# ESP32.net
KiCad netlist of a schematic drawn in Altium Designer
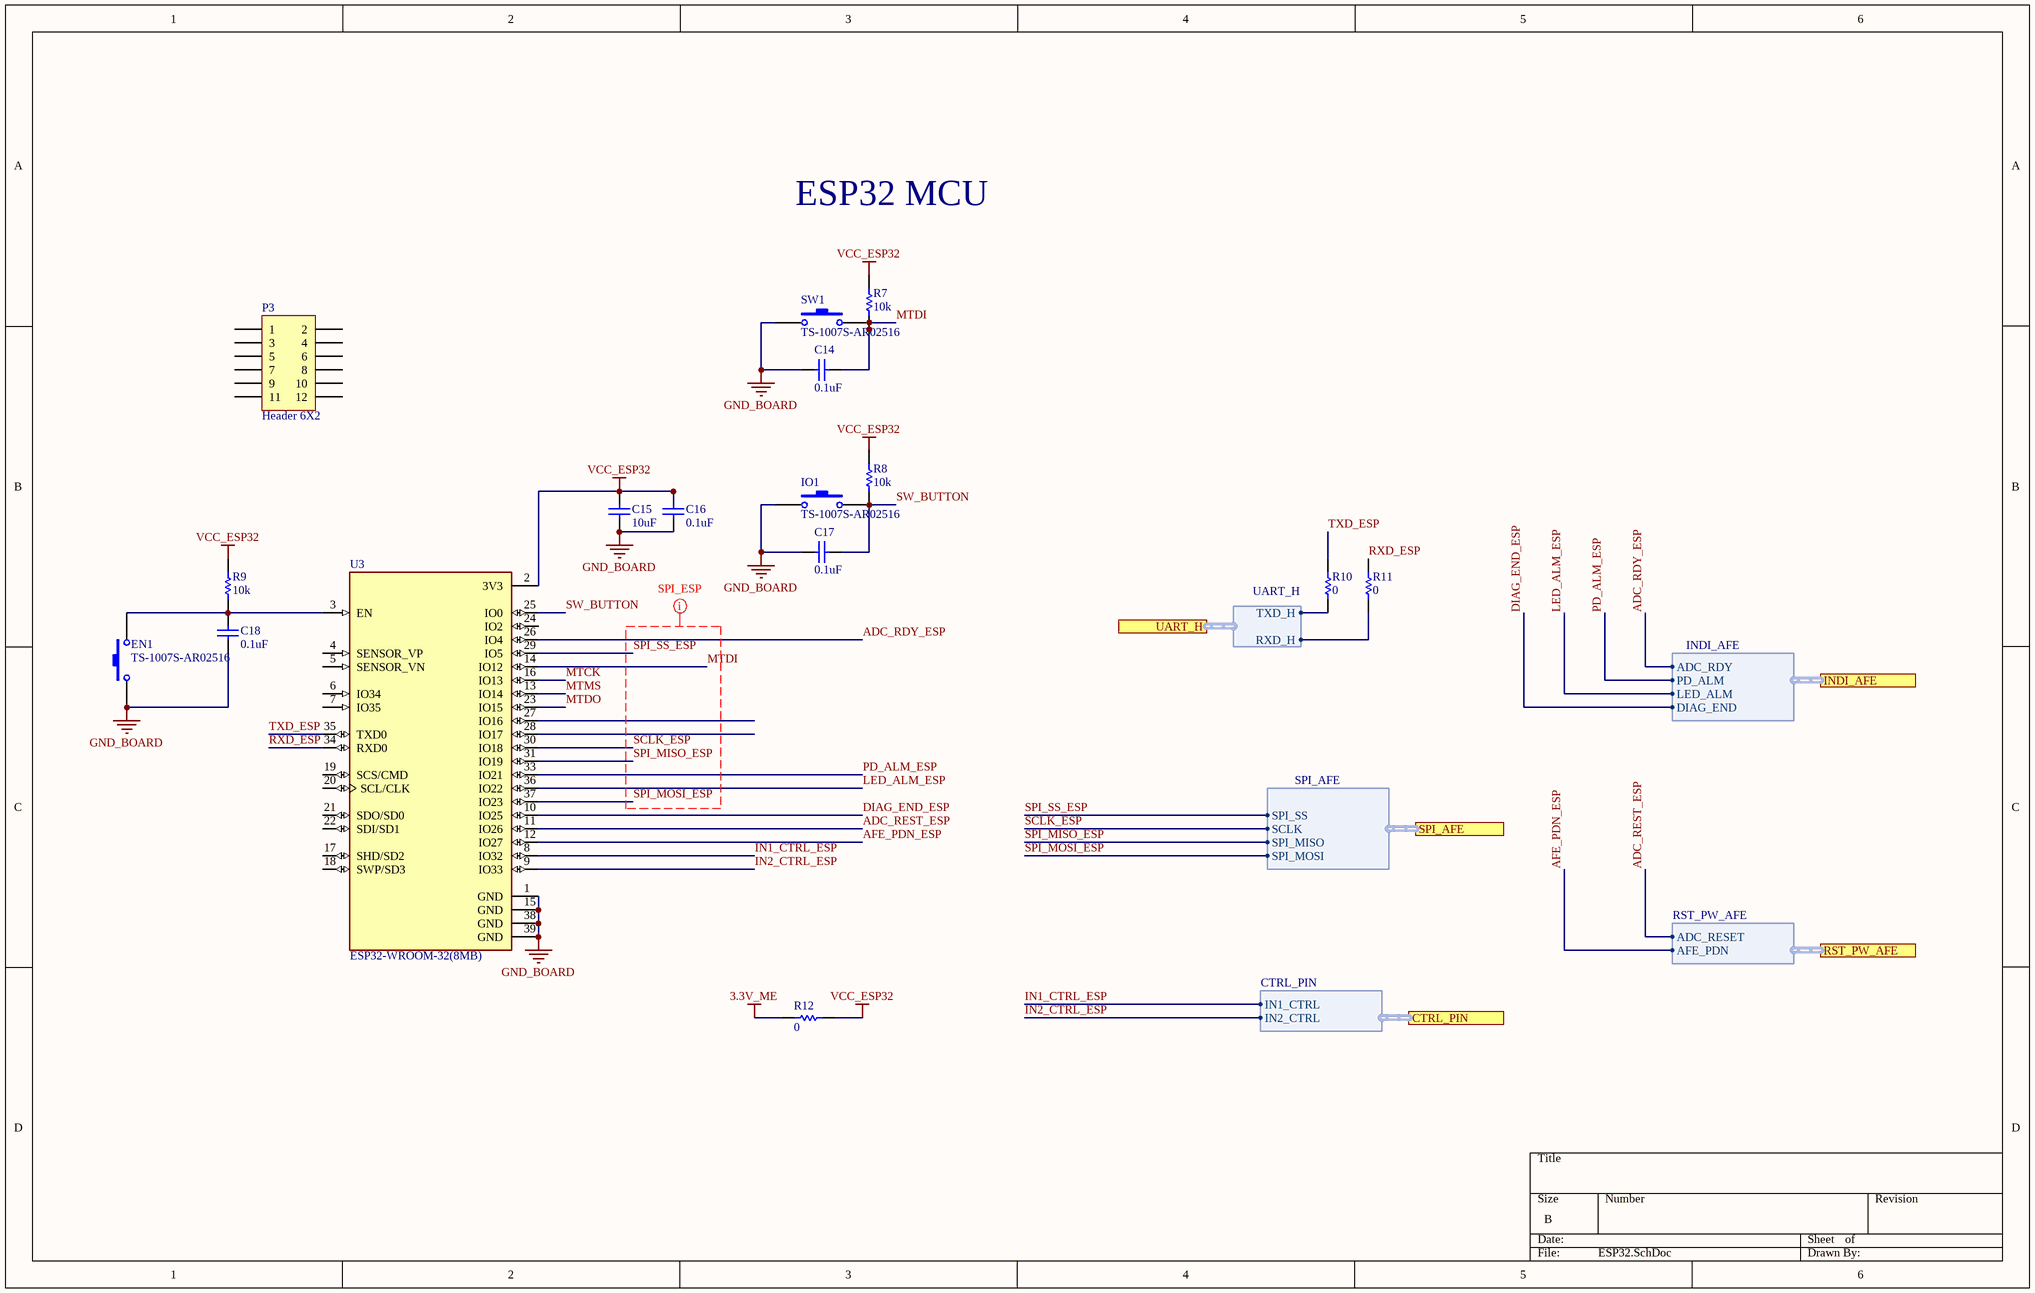
[diagram p0: ESP32.SchDoc]

(export (version "E")
  (design (tool "Eeschema 10.0.6"))
  (components
    (comp (ref "C14")
      (value "0.1uF")
      (footprint "RES-SMD-0603")
      (description "Capacitor")
      (fields (field (name "Comment") "Cap") (field (name "PUBLISHER") "Altium Limited"))
      (libsource (lib "Miscellaneous Devices") (part "Cap"))
    )
    (comp (ref "C15")
      (value "10uF")
      (footprint "RES-SMD-0603")
      (description "Capacitor")
      (fields (field (name "Comment") "Cap") (field (name "PUBLISHER") "Altium Limited"))
      (libsource (lib "Miscellaneous Devices") (part "Cap"))
    )
    (comp (ref "C16")
      (value "0.1uF")
      (footprint "RES-SMD-0603")
      (description "Capacitor")
      (fields (field (name "Comment") "Cap") (field (name "PUBLISHER") "Altium Limited"))
      (libsource (lib "Miscellaneous Devices") (part "Cap"))
    )
    (comp (ref "C17")
      (value "0.1uF")
      (footprint "RES-SMD-0603")
      (description "Capacitor")
      (fields (field (name "Comment") "Cap") (field (name "PUBLISHER") "Altium Limited"))
      (libsource (lib "Miscellaneous Devices") (part "Cap"))
    )
    (comp (ref "C18")
      (value "0.1uF")
      (footprint "RES-SMD-0603")
      (description "Capacitor")
      (fields (field (name "Comment") "Cap") (field (name "PUBLISHER") "Altium Limited"))
      (libsource (lib "Miscellaneous Devices") (part "Cap"))
    )
    (comp (ref "EN1")
      (value "TS-1007S-AR02516")
      (footprint "SW1_SMD")
      (description "Switch")
      (fields (field (name "PUBLISHER") "Altium Limited"))
      (libsource (lib "Miscellaneous Devices") (part "SW-PB"))
    )
    (comp (ref "IO1")
      (value "TS-1007S-AR02516")
      (footprint "SW1_SMD")
      (description "Switch")
      (fields (field (name "PUBLISHER") "Altium Limited"))
      (libsource (lib "Miscellaneous Devices") (part "SW-PB"))
    )
    (comp (ref "P3")
      (value "Header 6X2")
      (footprint "HDR2X6")
      (description "Header, 6-Pin, Dual row")
      (fields (field (name "PUBLISHER") "Altium Limited"))
      (libsource (lib "Miscellaneous Connectors") (part "Header 6X2"))
    )
    (comp (ref "R7")
      (value "10k")
      (footprint "RES-SMD-0603")
      (description "Resistor")
      (fields (field (name "Comment") "Res1") (field (name "PUBLISHER") "Altium Limited"))
      (libsource (lib "Miscellaneous Devices") (part "Res1"))
    )
    (comp (ref "R8")
      (value "10k")
      (footprint "RES-SMD-0603")
      (description "Resistor")
      (fields (field (name "Comment") "Res1") (field (name "PUBLISHER") "Altium Limited"))
      (libsource (lib "Miscellaneous Devices") (part "Res1"))
    )
    (comp (ref "R9")
      (value "10k")
      (footprint "RES-SMD-0603")
      (description "Resistor")
      (fields (field (name "Comment") "Res1") (field (name "PUBLISHER") "Altium Limited"))
      (libsource (lib "Miscellaneous Devices") (part "Res1"))
    )
    (comp (ref "R10")
      (value "0")
      (footprint "RES-SMD-0603")
      (description "Resistor")
      (fields (field (name "Comment") "Res1") (field (name "PUBLISHER") "Altium Limited"))
      (libsource (lib "Miscellaneous Devices") (part "Res1"))
    )
    (comp (ref "R11")
      (value "0")
      (footprint "RES-SMD-0603")
      (description "Resistor")
      (fields (field (name "Comment") "Res1") (field (name "PUBLISHER") "Altium Limited"))
      (libsource (lib "Miscellaneous Devices") (part "Res1"))
    )
    (comp (ref "R12")
      (value "0")
      (footprint "RES-SMD-0603")
      (description "Resistor")
      (fields (field (name "Comment") "Res1") (field (name "PUBLISHER") "Altium Limited"))
      (libsource (lib "Miscellaneous Devices") (part "Res1"))
    )
    (comp (ref "SW1")
      (value "TS-1007S-AR02516")
      (footprint "SW1_SMD")
      (description "Switch")
      (fields (field (name "PUBLISHER") "Altium Limited"))
      (libsource (lib "Miscellaneous Devices") (part "SW-PB"))
    )
    (comp (ref "U3")
      (value "ESP32-WROOM-32(8MB)")
      (footprint "MODULE_ESP32-WROOM-32(8MB)")
      (fields (field (name "MF") "Espressif Systems") (field (name "MP") "ESP32-WROOM-32 _8MB_"))
      (libsource (lib "SnapEDAsch") (part "ESP32-WROOM-32(8MB)"))
    )
  )
  (nets
    (net (code "6") (name "/ADC_RDY_ESP") (class "Default")
      (node (ref "U3") (pin "26") (pinfunction "IO4_26") (pintype "bidirectional"))
    )
    (net (code "7") (name "/ADC_REST_ESP") (class "Default")
      (node (ref "U3") (pin "11") (pinfunction "IO26_11") (pintype "bidirectional"))
    )
    (net (code "8") (name "/AFE_PDN_ESP") (class "Default")
      (node (ref "U3") (pin "12") (pinfunction "IO27_12") (pintype "bidirectional"))
    )
    (net (code "9") (name "/DIAG_END_ESP") (class "Default")
      (node (ref "U3") (pin "10") (pinfunction "IO25_10") (pintype "bidirectional"))
    )
    (net (code "10") (name "/IN1_CTRL_ESP") (class "Default")
      (node (ref "U3") (pin "8") (pinfunction "IO32_8") (pintype "bidirectional"))
    )
    (net (code "11") (name "/IN2_CTRL_ESP") (class "Default")
      (node (ref "U3") (pin "9") (pinfunction "IO33_9") (pintype "bidirectional"))
    )
    (net (code "12") (name "/LED_ALM_ESP") (class "Default")
      (node (ref "U3") (pin "36") (pinfunction "IO22_36") (pintype "bidirectional"))
    )
    (net (code "13") (name "/MTCK") (class "Default")
      (node (ref "U3") (pin "16") (pinfunction "IO13_16") (pintype "bidirectional"))
    )
    (net (code "14") (name "/MTDI") (class "Default")
      (node (ref "C14") (pin "1") (pinfunction "1_1") (pintype "passive"))
      (node (ref "R7") (pin "2") (pinfunction "2_2") (pintype "passive"))
      (node (ref "SW1") (pin "2") (pinfunction "2_2") (pintype "passive"))
      (node (ref "U3") (pin "14") (pinfunction "IO12_14") (pintype "bidirectional"))
    )
    (net (code "15") (name "/MTDO") (class "Default")
      (node (ref "U3") (pin "23") (pinfunction "IO15_23") (pintype "bidirectional"))
    )
    (net (code "16") (name "/MTMS") (class "Default")
      (node (ref "U3") (pin "13") (pinfunction "IO14_13") (pintype "bidirectional"))
    )
    (net (code "17") (name "/PD_ALM_ESP") (class "Default")
      (node (ref "U3") (pin "33") (pinfunction "IO21_33") (pintype "bidirectional"))
    )
    (net (code "18") (name "/RXD_ESP") (class "Default")
      (node (ref "R11") (pin "2") (pinfunction "2_2") (pintype "passive"))
      (node (ref "U3") (pin "34") (pinfunction "RXD0_34") (pintype "bidirectional"))
    )
    (net (code "19") (name "/RXD_H") (class "Default")
      (node (ref "R11") (pin "1") (pinfunction "1_1") (pintype "passive"))
    )
    (net (code "20") (name "/SCLK_ESP") (class "Default")
      (node (ref "U3") (pin "30") (pinfunction "IO18_30") (pintype "bidirectional"))
    )
    (net (code "21") (name "/SPI_MISO_ESP") (class "Default")
      (node (ref "U3") (pin "31") (pinfunction "IO19_31") (pintype "bidirectional"))
    )
    (net (code "22") (name "/SPI_MOSI_ESP") (class "Default")
      (node (ref "U3") (pin "37") (pinfunction "IO23_37") (pintype "bidirectional"))
    )
    (net (code "23") (name "/SPI_SS_ESP") (class "Default")
      (node (ref "U3") (pin "29") (pinfunction "IO5_29") (pintype "bidirectional"))
    )
    (net (code "24") (name "/SW_BUTTON") (class "Default")
      (node (ref "C17") (pin "1") (pinfunction "1_1") (pintype "passive"))
      (node (ref "IO1") (pin "2") (pinfunction "2_2") (pintype "passive"))
      (node (ref "R8") (pin "2") (pinfunction "2_2") (pintype "passive"))
      (node (ref "U3") (pin "25") (pinfunction "IO0_25") (pintype "bidirectional"))
    )
    (net (code "25") (name "/TXD_ESP") (class "Default")
      (node (ref "R10") (pin "2") (pinfunction "2_2") (pintype "passive"))
      (node (ref "U3") (pin "35") (pinfunction "TXD0_35") (pintype "bidirectional"))
    )
    (net (code "26") (name "/TXD_H") (class "Default")
      (node (ref "R10") (pin "1") (pinfunction "1_1") (pintype "passive"))
    )
    (net (code "32") (name "3.3V_ME") (class "Default")
      (node (ref "R12") (pin "2") (pinfunction "2_2") (pintype "passive"))
    )
    (net (code "33") (name "GND_BOARD") (class "Default")
      (node (ref "C14") (pin "2") (pinfunction "2_2") (pintype "passive"))
      (node (ref "C15") (pin "1") (pinfunction "1_1") (pintype "passive"))
      (node (ref "C16") (pin "1") (pinfunction "1_1") (pintype "passive"))
      (node (ref "C17") (pin "2") (pinfunction "2_2") (pintype "passive"))
      (node (ref "C18") (pin "1") (pinfunction "1_1") (pintype "passive"))
      (node (ref "EN1") (pin "1") (pinfunction "1_1") (pintype "passive"))
      (node (ref "IO1") (pin "1") (pinfunction "1_1") (pintype "passive"))
      (node (ref "SW1") (pin "1") (pinfunction "1_1") (pintype "passive"))
      (node (ref "U3") (pin "1") (pinfunction "GND_1") (pintype "power_in"))
      (node (ref "U3") (pin "15") (pinfunction "GND_15") (pintype "power_in"))
      (node (ref "U3") (pin "38") (pinfunction "GND_38") (pintype "power_in"))
      (node (ref "U3") (pin "39") (pinfunction "GND_39") (pintype "power_in"))
    )
    (net (code "34") (name "Net-(U3-EN)") (class "Default")
      (node (ref "C18") (pin "2") (pinfunction "2_2") (pintype "passive"))
      (node (ref "EN1") (pin "2") (pinfunction "2_2") (pintype "passive"))
      (node (ref "R9") (pin "2") (pinfunction "2_2") (pintype "passive"))
      (node (ref "U3") (pin "3") (pinfunction "EN_3") (pintype "input"))
    )
    (net (code "35") (name "VCC_ESP32") (class "Default")
      (node (ref "C15") (pin "2") (pinfunction "2_2") (pintype "passive"))
      (node (ref "C16") (pin "2") (pinfunction "2_2") (pintype "passive"))
      (node (ref "R12") (pin "1") (pinfunction "1_1") (pintype "passive"))
      (node (ref "R7") (pin "1") (pinfunction "1_1") (pintype "passive"))
      (node (ref "R8") (pin "1") (pinfunction "1_1") (pintype "passive"))
      (node (ref "R9") (pin "1") (pinfunction "1_1") (pintype "passive"))
      (node (ref "U3") (pin "2") (pinfunction "3V3_2") (pintype "power_in"))
    )
    (net (code "36") (name "unconnected-(P3-Pad1)") (class "Default")
      (node (ref "P3") (pin "1") (pinfunction "1_1") (pintype "passive"))
    )
    (net (code "37") (name "unconnected-(P3-Pad2)") (class "Default")
      (node (ref "P3") (pin "2") (pinfunction "2_2") (pintype "passive"))
    )
    (net (code "38") (name "unconnected-(P3-Pad3)") (class "Default")
      (node (ref "P3") (pin "3") (pinfunction "3_3") (pintype "passive"))
    )
    (net (code "39") (name "unconnected-(P3-Pad4)") (class "Default")
      (node (ref "P3") (pin "4") (pinfunction "4_4") (pintype "passive"))
    )
    (net (code "40") (name "unconnected-(P3-Pad5)") (class "Default")
      (node (ref "P3") (pin "5") (pinfunction "5_5") (pintype "passive"))
    )
    (net (code "41") (name "unconnected-(P3-Pad6)") (class "Default")
      (node (ref "P3") (pin "6") (pinfunction "6_6") (pintype "passive"))
    )
    (net (code "42") (name "unconnected-(P3-Pad7)") (class "Default")
      (node (ref "P3") (pin "7") (pinfunction "7_7") (pintype "passive"))
    )
    (net (code "43") (name "unconnected-(P3-Pad8)") (class "Default")
      (node (ref "P3") (pin "8") (pinfunction "8_8") (pintype "passive"))
    )
    (net (code "44") (name "unconnected-(P3-Pad9)") (class "Default")
      (node (ref "P3") (pin "9") (pinfunction "9_9") (pintype "passive"))
    )
    (net (code "45") (name "unconnected-(P3-Pad10)") (class "Default")
      (node (ref "P3") (pin "10") (pinfunction "10_10") (pintype "passive"))
    )
    (net (code "46") (name "unconnected-(P3-Pad11)") (class "Default")
      (node (ref "P3") (pin "11") (pinfunction "11_11") (pintype "passive"))
    )
    (net (code "47") (name "unconnected-(P3-Pad12)") (class "Default")
      (node (ref "P3") (pin "12") (pinfunction "12_12") (pintype "passive"))
    )
    (net (code "48") (name "unconnected-(U3-IO2-Pad24)") (class "Default")
      (node (ref "U3") (pin "24") (pinfunction "IO2_24") (pintype "bidirectional"))
    )
    (net (code "49") (name "unconnected-(U3-IO16-Pad27)") (class "Default")
      (node (ref "U3") (pin "27") (pinfunction "IO16_27") (pintype "bidirectional"))
    )
    (net (code "50") (name "unconnected-(U3-IO17-Pad28)") (class "Default")
      (node (ref "U3") (pin "28") (pinfunction "IO17_28") (pintype "bidirectional"))
    )
    (net (code "51") (name "unconnected-(U3-IO34-Pad6)") (class "Default")
      (node (ref "U3") (pin "6") (pinfunction "IO34_6") (pintype "input"))
    )
    (net (code "52") (name "unconnected-(U3-IO35-Pad7)") (class "Default")
      (node (ref "U3") (pin "7") (pinfunction "IO35_7") (pintype "input"))
    )
    (net (code "53") (name "unconnected-(U3-SCL{slash}CLK-Pad20)") (class "Default")
      (node (ref "U3") (pin "20") (pinfunction "SCL/CLK_20") (pintype "bidirectional"))
    )
    (net (code "54") (name "unconnected-(U3-SCS{slash}CMD-Pad19)") (class "Default")
      (node (ref "U3") (pin "19") (pinfunction "SCS/CMD_19") (pintype "bidirectional"))
    )
    (net (code "55") (name "unconnected-(U3-SDI{slash}SD1-Pad22)") (class "Default")
      (node (ref "U3") (pin "22") (pinfunction "SDI/SD1_22") (pintype "bidirectional"))
    )
    (net (code "56") (name "unconnected-(U3-SDO{slash}SD0-Pad21)") (class "Default")
      (node (ref "U3") (pin "21") (pinfunction "SDO/SD0_21") (pintype "bidirectional"))
    )
    (net (code "57") (name "unconnected-(U3-SENSOR_VN-Pad5)") (class "Default")
      (node (ref "U3") (pin "5") (pinfunction "SENSOR_VN_5") (pintype "input"))
    )
    (net (code "58") (name "unconnected-(U3-SENSOR_VP-Pad4)") (class "Default")
      (node (ref "U3") (pin "4") (pinfunction "SENSOR_VP_4") (pintype "input"))
    )
    (net (code "59") (name "unconnected-(U3-SHD{slash}SD2-Pad17)") (class "Default")
      (node (ref "U3") (pin "17") (pinfunction "SHD/SD2_17") (pintype "bidirectional"))
    )
    (net (code "60") (name "unconnected-(U3-SWP{slash}SD3-Pad18)") (class "Default")
      (node (ref "U3") (pin "18") (pinfunction "SWP/SD3_18") (pintype "bidirectional"))
    )
  )
)
